# ECG_V2.net
KiCad netlist of a schematic drawn in EAGLE
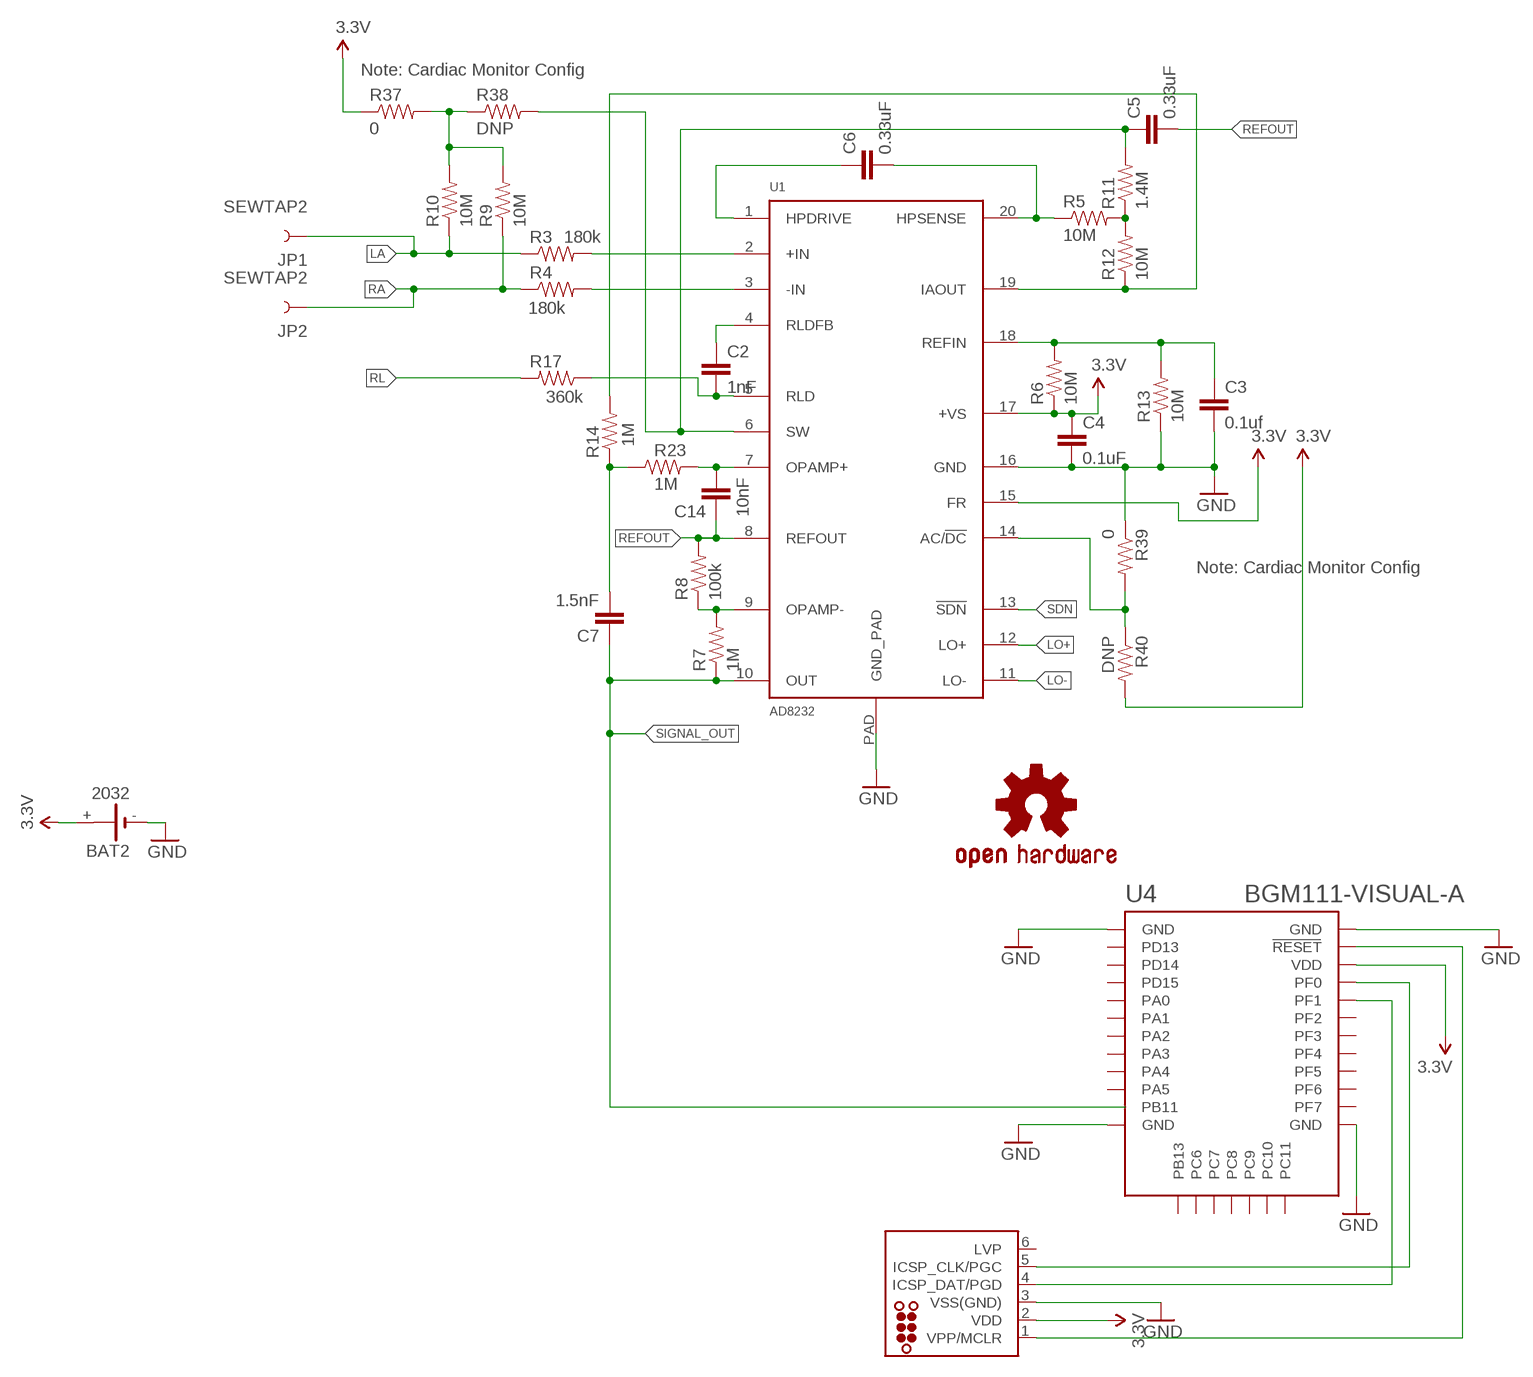
[diagram p0: schematic, sheet 1]

(export (version "E")
  (design (tool "Eeschema 10.0.6"))
  (components
    (comp (ref "BAT2")
      (value "2032")
      (footprint "eagle-import:KZH20SMD")
      (libsource (lib "eagle-import") (part "2032"))
    )
    (comp (ref "C2")
      (value "1nF")
      (footprint "eagle-import:0603-CAP")
      (libsource (lib "eagle-import") (part "CAP0603-CAP"))
    )
    (comp (ref "C3")
      (value "0.1uf")
      (footprint "eagle-import:0603-CAP")
      (libsource (lib "eagle-import") (part "CAP0603-CAP"))
    )
    (comp (ref "C4")
      (value "0.1uF")
      (footprint "eagle-import:0603-CAP")
      (libsource (lib "eagle-import") (part "CAP0603-CAP"))
    )
    (comp (ref "C5")
      (value "0.33uF")
      (footprint "eagle-import:0805")
      (libsource (lib "eagle-import") (part "CAP0805"))
    )
    (comp (ref "C6")
      (value "0.33uF")
      (footprint "eagle-import:0805")
      (libsource (lib "eagle-import") (part "CAP0805"))
    )
    (comp (ref "C7")
      (value "1.5nF")
      (footprint "eagle-import:0603-CAP")
      (libsource (lib "eagle-import") (part "CAP0603-CAP"))
    )
    (comp (ref "C14")
      (value "10nF")
      (footprint "eagle-import:0603-CAP")
      (libsource (lib "eagle-import") (part "CAP0603-CAP"))
    )
    (comp (ref "J1")
      (value "TC2030-MCP-NL")
      (footprint "eagle-import:TC2030-MCP-NL")
      (libsource (lib "eagle-import") (part "TC2030-MCP-NL"))
    )
    (comp (ref "JP1")
      (value "SEWTAP2")
      (footprint "eagle-import:PETAL-LONG-2")
      (libsource (lib "eagle-import") (part "SEWTAP2"))
    )
    (comp (ref "JP2")
      (value "SEWTAP2")
      (footprint "eagle-import:PETAL-LONG-2")
      (libsource (lib "eagle-import") (part "SEWTAP2"))
    )
    (comp (ref "LOGO3")
      (value "OSHW-LOGOS")
      (footprint "eagle-import:OSHW-LOGO-S")
      (libsource (lib "eagle-import") (part "OSHW-LOGOS"))
    )
    (comp (ref "R3")
      (value "180k")
      (footprint "eagle-import:0603-RES")
      (libsource (lib "eagle-import") (part "RESISTOR0603-RES"))
    )
    (comp (ref "R4")
      (value "180k")
      (footprint "eagle-import:0603-RES")
      (libsource (lib "eagle-import") (part "RESISTOR0603-RES"))
    )
    (comp (ref "R5")
      (value "10M")
      (footprint "eagle-import:0603-RES")
      (libsource (lib "eagle-import") (part "RESISTOR0603-RES"))
    )
    (comp (ref "R6")
      (value "10M")
      (footprint "eagle-import:0603-RES")
      (libsource (lib "eagle-import") (part "RESISTOR0603-RES"))
    )
    (comp (ref "R7")
      (value "1M")
      (footprint "eagle-import:0603-RES")
      (libsource (lib "eagle-import") (part "RESISTOR0603-RES"))
    )
    (comp (ref "R8")
      (value "100k")
      (footprint "eagle-import:0603-RES")
      (libsource (lib "eagle-import") (part "RESISTOR0603-RES"))
    )
    (comp (ref "R9")
      (value "10M")
      (footprint "eagle-import:0603-RES")
      (libsource (lib "eagle-import") (part "RESISTOR0603-RES"))
    )
    (comp (ref "R10")
      (value "10M")
      (footprint "eagle-import:0603-RES")
      (libsource (lib "eagle-import") (part "RESISTOR0603-RES"))
    )
    (comp (ref "R11")
      (value "1.4M")
      (footprint "eagle-import:0603-RES")
      (libsource (lib "eagle-import") (part "RESISTOR0603-RES"))
    )
    (comp (ref "R12")
      (value "10M")
      (footprint "eagle-import:0603-RES")
      (libsource (lib "eagle-import") (part "RESISTOR0603-RES"))
    )
    (comp (ref "R13")
      (value "10M")
      (footprint "eagle-import:0603-RES")
      (libsource (lib "eagle-import") (part "RESISTOR0603-RES"))
    )
    (comp (ref "R14")
      (value "1M")
      (footprint "eagle-import:0603-RES")
      (libsource (lib "eagle-import") (part "RESISTOR0603-RES"))
    )
    (comp (ref "R17")
      (value "360k")
      (footprint "eagle-import:0603-RES")
      (libsource (lib "eagle-import") (part "RESISTOR0603-RES"))
    )
    (comp (ref "R23")
      (value "1M")
      (footprint "eagle-import:0603-RES")
      (libsource (lib "eagle-import") (part "RESISTOR0603-RES"))
    )
    (comp (ref "R37")
      (value "0")
      (footprint "eagle-import:0603")
      (libsource (lib "eagle-import") (part "0OHM1/10W5%(0603)"))
    )
    (comp (ref "R38")
      (value "DNP")
      (footprint "eagle-import:0603")
      (libsource (lib "eagle-import") (part "0OHM1/10W5%(0603)"))
    )
    (comp (ref "R39")
      (value "0")
      (footprint "eagle-import:0603")
      (libsource (lib "eagle-import") (part "0OHM1/10W5%(0603)"))
    )
    (comp (ref "R40")
      (value "DNP")
      (footprint "eagle-import:0603")
      (libsource (lib "eagle-import") (part "0OHM1/10W5%(0603)"))
    )
    (comp (ref "U1")
      (value "AD8232")
      (footprint "eagle-import:LFCSP_20")
      (libsource (lib "eagle-import") (part "AD8232"))
    )
    (comp (ref "U4")
      (value "BGM111-VISUAL-A")
      (footprint "eagle-import:BGM111-A")
      (libsource (lib "eagle-import") (part "BGM111-VISUAL-A"))
    )
  )
  (nets
    (net (code "1") (name "3.3V") (class "Default")
      (node (ref "BAT2") (pin "+") (pinfunction "+_+") (pintype "passive"))
      (node (ref "C4") (pin "1") (pinfunction "1_1") (pintype "passive"))
      (node (ref "J1") (pin "2") (pinfunction "VDD_2") (pintype "power_in"))
      (node (ref "R37") (pin "1") (pinfunction "1_1") (pintype "passive"))
      (node (ref "R40") (pin "2") (pinfunction "2_2") (pintype "passive"))
      (node (ref "R6") (pin "1") (pinfunction "1_1") (pintype "passive"))
      (node (ref "U1") (pin "15") (pinfunction "FR_15") (pintype "bidirectional"))
      (node (ref "U1") (pin "17") (pinfunction "+VS_17") (pintype "bidirectional"))
      (node (ref "U4") (pin "VDD") (pinfunction "VDD_VDD") (pintype "power_in"))
    )
    (net (code "2") (name "GND") (class "Default")
      (node (ref "BAT2") (pin "-") (pinfunction "-_-") (pintype "passive"))
      (node (ref "C3") (pin "2") (pinfunction "2_2") (pintype "passive"))
      (node (ref "C4") (pin "2") (pinfunction "2_2") (pintype "passive"))
      (node (ref "J1") (pin "3") (pinfunction "VSS(GND)_3") (pintype "power_in"))
      (node (ref "R13") (pin "1") (pinfunction "1_1") (pintype "passive"))
      (node (ref "R39") (pin "1") (pinfunction "1_1") (pintype "passive"))
      (node (ref "U1") (pin "16") (pinfunction "GND_16") (pintype "bidirectional"))
      (node (ref "U1") (pin "PAD") (pinfunction "GND_PAD_PAD") (pintype "bidirectional"))
      (node (ref "U4") (pin "GND") (pinfunction "GND_GND") (pintype "power_in"))
      (node (ref "U4") (pin "GND@2") (pinfunction "GND_GND@2") (pintype "power_in"))
      (node (ref "U4") (pin "GND@3") (pinfunction "GND_GND@3") (pintype "power_in"))
      (node (ref "U4") (pin "GND@4") (pinfunction "GND_GND@4") (pintype "power_in"))
    )
    (net (code "3") (name "LA") (class "Default")
      (node (ref "JP1") (pin "1") (pinfunction "1_1") (pintype "bidirectional"))
      (node (ref "R10") (pin "1") (pinfunction "1_1") (pintype "passive"))
      (node (ref "R3") (pin "1") (pinfunction "1_1") (pintype "passive"))
    )
    (net (code "4") (name "LO+") (class "Default")
      (node (ref "U1") (pin "12") (pinfunction "LO+_12") (pintype "bidirectional"))
    )
    (net (code "5") (name "LO-") (class "Default")
      (node (ref "U1") (pin "11") (pinfunction "LO-_11") (pintype "bidirectional"))
    )
    (net (code "6") (name "Net-(C7-Pad2)") (class "Default")
      (node (ref "C7") (pin "2") (pinfunction "2_2") (pintype "passive"))
      (node (ref "R14") (pin "1") (pinfunction "1_1") (pintype "passive"))
      (node (ref "R23") (pin "1") (pinfunction "1_1") (pintype "passive"))
    )
    (net (code "7") (name "Net-(J1-ICSP_CLK{slash}PGC)") (class "Default")
      (node (ref "J1") (pin "5") (pinfunction "ICSP_CLK/PGC_5") (pintype "output"))
      (node (ref "U4") (pin "PF0") (pinfunction "PF0_PF0") (pintype "bidirectional"))
    )
    (net (code "8") (name "Net-(J1-ICSP_DAT{slash}PGD)") (class "Default")
      (node (ref "J1") (pin "4") (pinfunction "ICSP_DAT/PGD_4") (pintype "bidirectional"))
      (node (ref "U4") (pin "PF1") (pinfunction "PF1_PF1") (pintype "bidirectional"))
    )
    (net (code "9") (name "Net-(J1-VPP{slash}MCLR)") (class "Default")
      (node (ref "J1") (pin "1") (pinfunction "VPP/MCLR_1") (pintype "passive"))
      (node (ref "U4") (pin "RESET") (pinfunction "RESET_RESET") (pintype "input"))
    )
    (net (code "10") (name "Net-(R10-Pad2)") (class "Default")
      (node (ref "R10") (pin "2") (pinfunction "2_2") (pintype "passive"))
      (node (ref "R37") (pin "2") (pinfunction "2_2") (pintype "passive"))
      (node (ref "R38") (pin "1") (pinfunction "1_1") (pintype "passive"))
      (node (ref "R9") (pin "2") (pinfunction "2_2") (pintype "passive"))
    )
    (net (code "11") (name "Net-(R11-Pad1)") (class "Default")
      (node (ref "R11") (pin "1") (pinfunction "1_1") (pintype "passive"))
      (node (ref "R12") (pin "2") (pinfunction "2_2") (pintype "passive"))
      (node (ref "R5") (pin "2") (pinfunction "2_2") (pintype "passive"))
    )
    (net (code "12") (name "Net-(U1-+IN)") (class "Default")
      (node (ref "R3") (pin "2") (pinfunction "2_2") (pintype "passive"))
      (node (ref "U1") (pin "2") (pinfunction "+IN_2") (pintype "bidirectional"))
    )
    (net (code "13") (name "Net-(U1--IN)") (class "Default")
      (node (ref "R4") (pin "2") (pinfunction "2_2") (pintype "passive"))
      (node (ref "U1") (pin "3") (pinfunction "-IN_3") (pintype "bidirectional"))
    )
    (net (code "14") (name "Net-(U1-AC{slash}~{DC})") (class "Default")
      (node (ref "R39") (pin "2") (pinfunction "2_2") (pintype "passive"))
      (node (ref "R40") (pin "1") (pinfunction "1_1") (pintype "passive"))
      (node (ref "U1") (pin "14") (pinfunction "AC/~{DC}_14") (pintype "bidirectional"))
    )
    (net (code "15") (name "Net-(U1-HPDRIVE)") (class "Default")
      (node (ref "C6") (pin "1") (pinfunction "1_1") (pintype "passive"))
      (node (ref "U1") (pin "1") (pinfunction "HPDRIVE_1") (pintype "bidirectional"))
    )
    (net (code "16") (name "Net-(U1-HPSENSE)") (class "Default")
      (node (ref "C6") (pin "2") (pinfunction "2_2") (pintype "passive"))
      (node (ref "R5") (pin "1") (pinfunction "1_1") (pintype "passive"))
      (node (ref "U1") (pin "20") (pinfunction "HPSENSE_20") (pintype "bidirectional"))
    )
    (net (code "17") (name "Net-(U1-IAOUT)") (class "Default")
      (node (ref "R12") (pin "1") (pinfunction "1_1") (pintype "passive"))
      (node (ref "R14") (pin "2") (pinfunction "2_2") (pintype "passive"))
      (node (ref "U1") (pin "19") (pinfunction "IAOUT_19") (pintype "bidirectional"))
    )
    (net (code "18") (name "Net-(U1-OPAMP+)") (class "Default")
      (node (ref "C14") (pin "2") (pinfunction "2_2") (pintype "passive"))
      (node (ref "R23") (pin "2") (pinfunction "2_2") (pintype "passive"))
      (node (ref "U1") (pin "7") (pinfunction "OPAMP+_7") (pintype "bidirectional"))
    )
    (net (code "19") (name "Net-(U1-OPAMP-)") (class "Default")
      (node (ref "R7") (pin "2") (pinfunction "2_2") (pintype "passive"))
      (node (ref "R8") (pin "1") (pinfunction "1_1") (pintype "passive"))
      (node (ref "U1") (pin "9") (pinfunction "OPAMP-_9") (pintype "bidirectional"))
    )
    (net (code "20") (name "Net-(U1-REFIN)") (class "Default")
      (node (ref "C3") (pin "1") (pinfunction "1_1") (pintype "passive"))
      (node (ref "R13") (pin "2") (pinfunction "2_2") (pintype "passive"))
      (node (ref "R6") (pin "2") (pinfunction "2_2") (pintype "passive"))
      (node (ref "U1") (pin "18") (pinfunction "REFIN_18") (pintype "bidirectional"))
    )
    (net (code "21") (name "Net-(U1-RLD)") (class "Default")
      (node (ref "C2") (pin "2") (pinfunction "2_2") (pintype "passive"))
      (node (ref "R17") (pin "1") (pinfunction "1_1") (pintype "passive"))
      (node (ref "U1") (pin "5") (pinfunction "RLD_5") (pintype "bidirectional"))
    )
    (net (code "22") (name "Net-(U1-RLDFB)") (class "Default")
      (node (ref "C2") (pin "1") (pinfunction "1_1") (pintype "passive"))
      (node (ref "U1") (pin "4") (pinfunction "RLDFB_4") (pintype "bidirectional"))
    )
    (net (code "23") (name "Net-(U1-SW)") (class "Default")
      (node (ref "C5") (pin "1") (pinfunction "1_1") (pintype "passive"))
      (node (ref "R11") (pin "2") (pinfunction "2_2") (pintype "passive"))
      (node (ref "R38") (pin "2") (pinfunction "2_2") (pintype "passive"))
      (node (ref "U1") (pin "6") (pinfunction "SW_6") (pintype "bidirectional"))
    )
    (net (code "24") (name "RA") (class "Default")
      (node (ref "JP2") (pin "1") (pinfunction "1_1") (pintype "bidirectional"))
      (node (ref "R4") (pin "1") (pinfunction "1_1") (pintype "passive"))
      (node (ref "R9") (pin "1") (pinfunction "1_1") (pintype "passive"))
    )
    (net (code "25") (name "REFOUT") (class "Default")
      (node (ref "C14") (pin "1") (pinfunction "1_1") (pintype "passive"))
      (node (ref "C5") (pin "2") (pinfunction "2_2") (pintype "passive"))
      (node (ref "R8") (pin "2") (pinfunction "2_2") (pintype "passive"))
      (node (ref "U1") (pin "8") (pinfunction "REFOUT_8") (pintype "bidirectional"))
    )
    (net (code "26") (name "RL") (class "Default")
      (node (ref "R17") (pin "2") (pinfunction "2_2") (pintype "passive"))
    )
    (net (code "27") (name "SDN") (class "Default")
      (node (ref "U1") (pin "13") (pinfunction "~{SDN}_13") (pintype "bidirectional"))
    )
    (net (code "28") (name "SIGNAL_OUT") (class "Default")
      (node (ref "C7") (pin "1") (pinfunction "1_1") (pintype "passive"))
      (node (ref "R7") (pin "1") (pinfunction "1_1") (pintype "passive"))
      (node (ref "U1") (pin "10") (pinfunction "OUT_10") (pintype "bidirectional"))
    )
    (net (code "29") (name "unconnected-(J1-LVP-Pad6)") (class "Default")
      (node (ref "J1") (pin "6") (pinfunction "LVP_6") (pintype "bidirectional"))
    )
    (net (code "30") (name "unconnected-(U4-PadPA0)") (class "Default")
      (node (ref "U4") (pin "PA0") (pinfunction "PA0_PA0") (pintype "bidirectional"))
    )
    (net (code "31") (name "unconnected-(U4-PadPA1)") (class "Default")
      (node (ref "U4") (pin "PA1") (pinfunction "PA1_PA1") (pintype "bidirectional"))
    )
    (net (code "32") (name "unconnected-(U4-PadPA2)") (class "Default")
      (node (ref "U4") (pin "PA2") (pinfunction "PA2_PA2") (pintype "bidirectional"))
    )
    (net (code "33") (name "unconnected-(U4-PadPA3)") (class "Default")
      (node (ref "U4") (pin "PA3") (pinfunction "PA3_PA3") (pintype "bidirectional"))
    )
    (net (code "34") (name "unconnected-(U4-PadPA4)") (class "Default")
      (node (ref "U4") (pin "PA4") (pinfunction "PA4_PA4") (pintype "bidirectional"))
    )
    (net (code "35") (name "unconnected-(U4-PadPA5)") (class "Default")
      (node (ref "U4") (pin "PA5") (pinfunction "PA5_PA5") (pintype "bidirectional"))
    )
    (net (code "36") (name "unconnected-(U4-PadPB11)") (class "Default")
      (node (ref "U4") (pin "PB11") (pinfunction "PB11_PB11") (pintype "bidirectional"))
    )
    (net (code "37") (name "unconnected-(U4-PadPB13)") (class "Default")
      (node (ref "U4") (pin "PB13") (pinfunction "PB13_PB13") (pintype "bidirectional"))
    )
    (net (code "38") (name "unconnected-(U4-PadPC6)") (class "Default")
      (node (ref "U4") (pin "PC6") (pinfunction "PC6_PC6") (pintype "bidirectional"))
    )
    (net (code "39") (name "unconnected-(U4-PadPC7)") (class "Default")
      (node (ref "U4") (pin "PC7") (pinfunction "PC7_PC7") (pintype "bidirectional"))
    )
    (net (code "40") (name "unconnected-(U4-PadPC8)") (class "Default")
      (node (ref "U4") (pin "PC8") (pinfunction "PC8_PC8") (pintype "bidirectional"))
    )
    (net (code "41") (name "unconnected-(U4-PadPC9)") (class "Default")
      (node (ref "U4") (pin "PC9") (pinfunction "PC9_PC9") (pintype "bidirectional"))
    )
    (net (code "42") (name "unconnected-(U4-PadPC10)") (class "Default")
      (node (ref "U4") (pin "PC10") (pinfunction "PC10_PC10") (pintype "bidirectional"))
    )
    (net (code "43") (name "unconnected-(U4-PadPC11)") (class "Default")
      (node (ref "U4") (pin "PC11") (pinfunction "PC11_PC11") (pintype "bidirectional"))
    )
    (net (code "44") (name "unconnected-(U4-PadPD13)") (class "Default")
      (node (ref "U4") (pin "PD13") (pinfunction "PD13_PD13") (pintype "bidirectional"))
    )
    (net (code "45") (name "unconnected-(U4-PadPD14)") (class "Default")
      (node (ref "U4") (pin "PD14") (pinfunction "PD14_PD14") (pintype "bidirectional"))
    )
    (net (code "46") (name "unconnected-(U4-PadPD15)") (class "Default")
      (node (ref "U4") (pin "PD15") (pinfunction "PD15_PD15") (pintype "bidirectional"))
    )
    (net (code "47") (name "unconnected-(U4-PadPF2)") (class "Default")
      (node (ref "U4") (pin "PF2") (pinfunction "PF2_PF2") (pintype "bidirectional"))
    )
    (net (code "48") (name "unconnected-(U4-PadPF3)") (class "Default")
      (node (ref "U4") (pin "PF3") (pinfunction "PF3_PF3") (pintype "bidirectional"))
    )
    (net (code "49") (name "unconnected-(U4-PadPF4)") (class "Default")
      (node (ref "U4") (pin "PF4") (pinfunction "PF4_PF4") (pintype "bidirectional"))
    )
    (net (code "50") (name "unconnected-(U4-PadPF5)") (class "Default")
      (node (ref "U4") (pin "PF5") (pinfunction "PF5_PF5") (pintype "bidirectional"))
    )
    (net (code "51") (name "unconnected-(U4-PadPF6)") (class "Default")
      (node (ref "U4") (pin "PF6") (pinfunction "PF6_PF6") (pintype "bidirectional"))
    )
    (net (code "52") (name "unconnected-(U4-PadPF7)") (class "Default")
      (node (ref "U4") (pin "PF7") (pinfunction "PF7_PF7") (pintype "bidirectional"))
    )
  )
)
